# m328plain.net
KiCad netlist of a schematic drawn in EAGLE
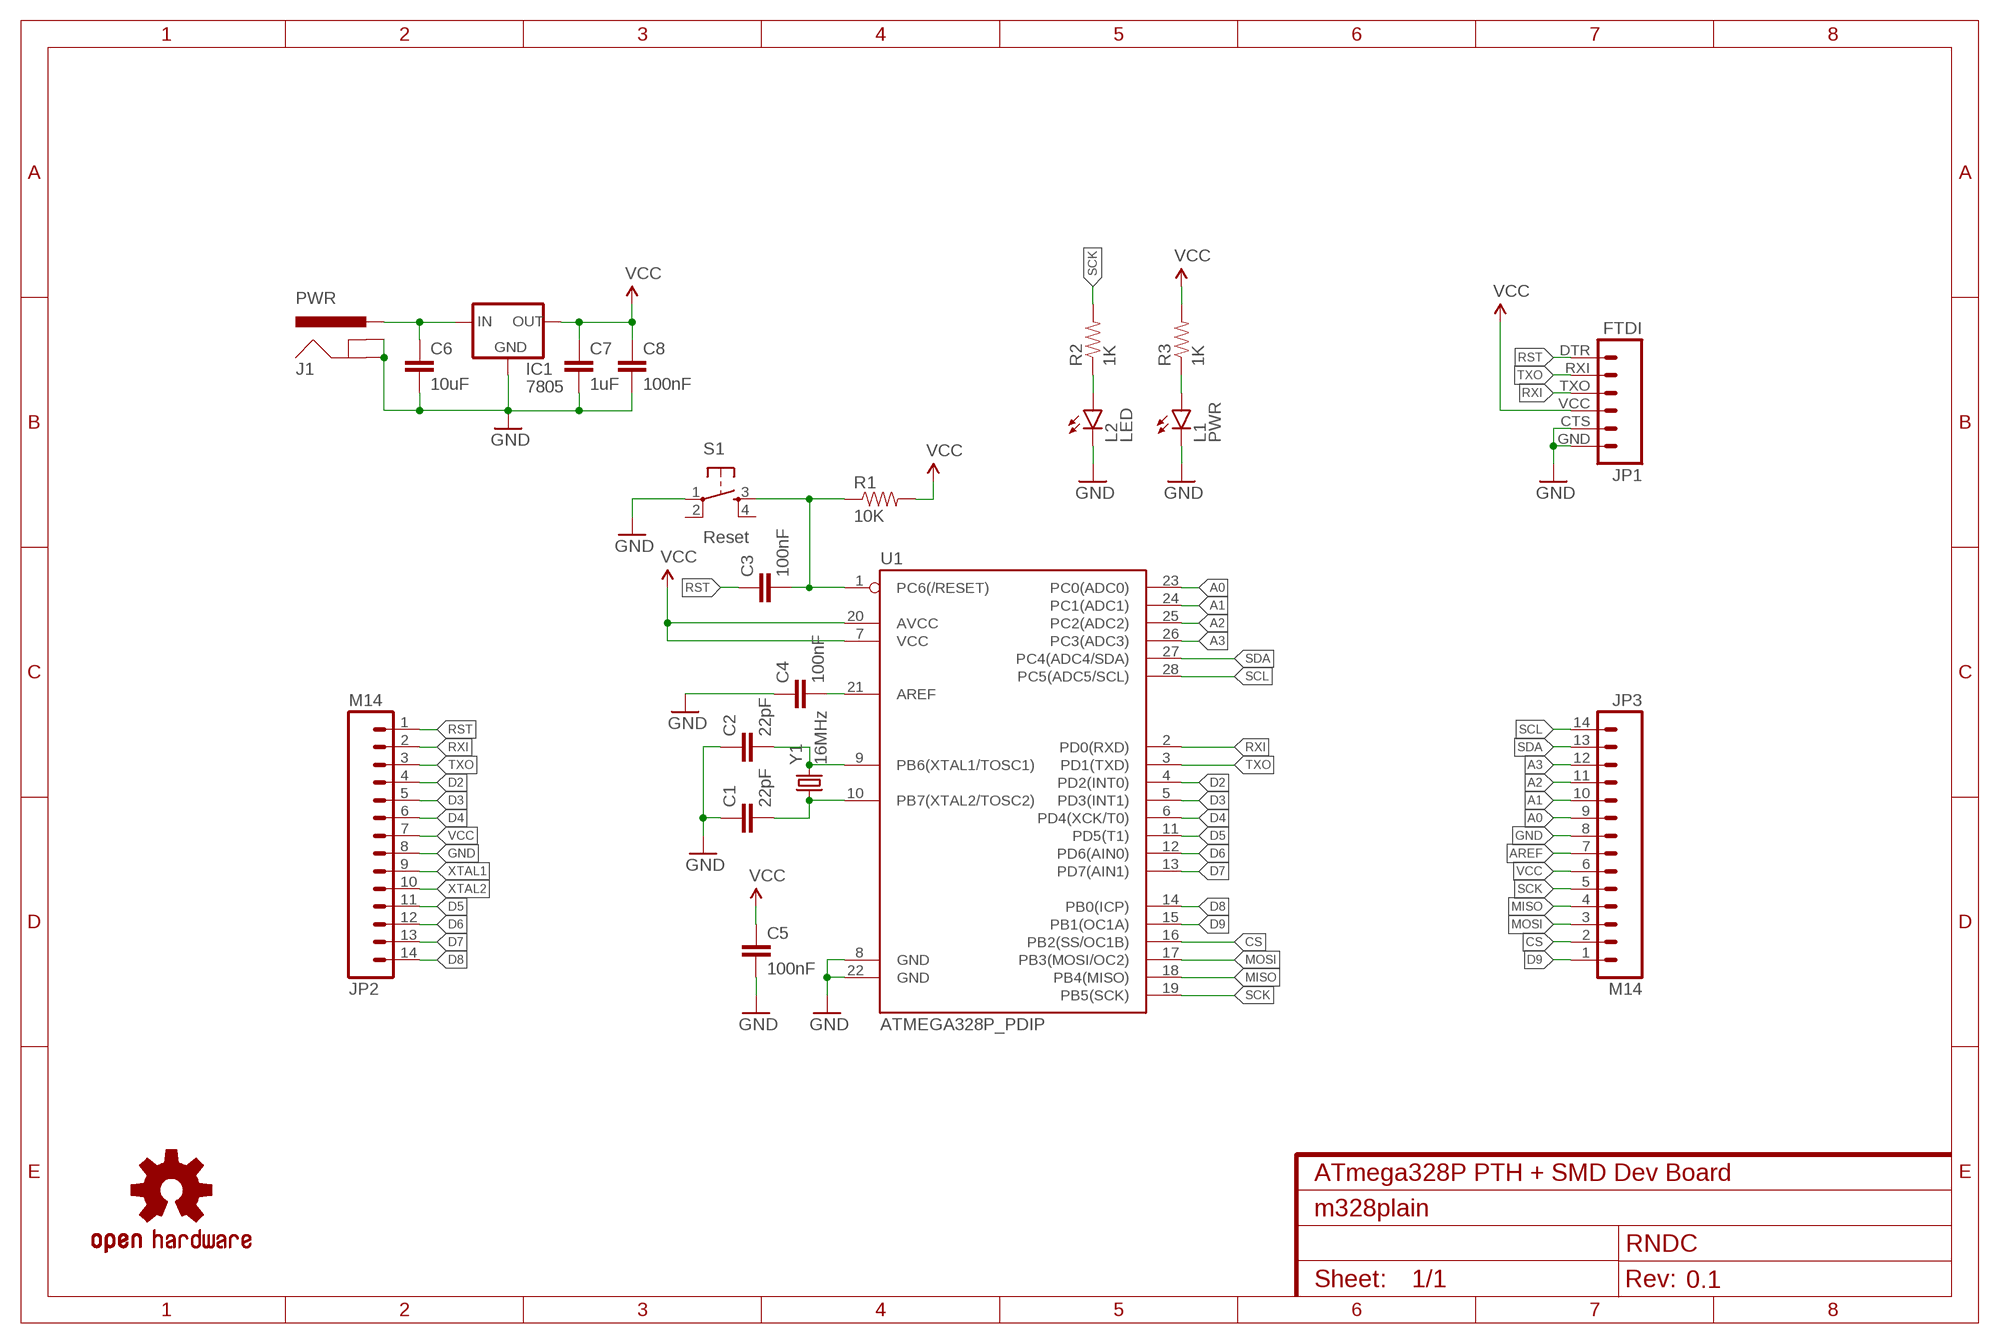
[diagram p0: schematic, sheet 1]

(export (version "E")
  (design (tool "Eeschema 10.0.6"))
  (components
    (comp (ref "C1")
      (value "22pF")
      (footprint "eagle-import:0805")
      (libsource (lib "eagle-import") (part "CAP0805"))
    )
    (comp (ref "C2")
      (value "22pF")
      (footprint "eagle-import:0805")
      (libsource (lib "eagle-import") (part "CAP0805"))
    )
    (comp (ref "C3")
      (value "100nF")
      (footprint "eagle-import:0805")
      (libsource (lib "eagle-import") (part "CAP0805"))
    )
    (comp (ref "C4")
      (value "100nF")
      (footprint "eagle-import:0805")
      (libsource (lib "eagle-import") (part "CAP0805"))
    )
    (comp (ref "C5")
      (value "100nF")
      (footprint "eagle-import:0805")
      (libsource (lib "eagle-import") (part "CAP0805"))
    )
    (comp (ref "C6")
      (value "10uF")
      (footprint "eagle-import:0603-CAP")
      (libsource (lib "eagle-import") (part "CAP0603-CAP"))
    )
    (comp (ref "C7")
      (value "1uF")
      (footprint "eagle-import:0603-CAP")
      (libsource (lib "eagle-import") (part "CAP0603-CAP"))
    )
    (comp (ref "C8")
      (value "100nF")
      (footprint "eagle-import:0805")
      (libsource (lib "eagle-import") (part "CAP0805"))
    )
    (comp (ref "IC1")
      (value "7805")
      (footprint "eagle-import:TO-92")
      (libsource (lib "eagle-import") (part "V_REG_78XXTO-92_UNTESTED"))
    )
    (comp (ref "J1")
      (value "PWR")
      (footprint "eagle-import:POWER_JACK_PTH")
      (libsource (lib "eagle-import") (part "POWER_JACKPTH"))
    )
    (comp (ref "JP1")
      (value "FTDI")
      (footprint "eagle-import:FTDI_BASIC")
      (libsource (lib "eagle-import") (part "FTDI_BASICPTH"))
    )
    (comp (ref "JP2")
      (value "M14")
      (footprint "eagle-import:1X14")
      (libsource (lib "eagle-import") (part "M14"))
    )
    (comp (ref "JP3")
      (value "M14")
      (footprint "eagle-import:1X14")
      (libsource (lib "eagle-import") (part "M14"))
    )
    (comp (ref "L1")
      (value "PWR")
      (footprint "eagle-import:LED3MM-NS")
      (libsource (lib "eagle-import") (part "LED-3MM-NO_SILK"))
    )
    (comp (ref "L2")
      (value "LED")
      (footprint "eagle-import:LED3MM-NS")
      (libsource (lib "eagle-import") (part "LED-3MM-NO_SILK"))
    )
    (comp (ref "LOGO1")
      (value "OSHW-LOGOL")
      (footprint "eagle-import:OSHW-LOGO-L")
      (libsource (lib "eagle-import") (part "OSHW-LOGOL"))
    )
    (comp (ref "R1")
      (value "10K")
      (footprint "eagle-import:0603-RES")
      (libsource (lib "eagle-import") (part "RESISTOR0603"))
    )
    (comp (ref "R2")
      (value "1K")
      (footprint "eagle-import:0603-RES")
      (libsource (lib "eagle-import") (part "RESISTOR0603-RES"))
    )
    (comp (ref "R3")
      (value "1K")
      (footprint "eagle-import:0603-RES")
      (libsource (lib "eagle-import") (part "RESISTOR0603-RES"))
    )
    (comp (ref "S1")
      (value "Reset")
      (footprint "eagle-import:TACTILE-PTH")
      (libsource (lib "eagle-import") (part "TAC_SWITCHPTH"))
    )
    (comp (ref "U1")
      (value "ATMEGA328P_PDIP")
      (footprint "eagle-import:DIL28-3")
      (libsource (lib "eagle-import") (part "ATMEGA328P_PDIP"))
    )
    (comp (ref "Y1")
      (value "16MHz")
      (footprint "eagle-import:HC49US")
      (libsource (lib "eagle-import") (part "CRYSTALHC49US"))
    )
  )
  (nets
    (net (code "1") (name "A0") (class "Default")
      (node (ref "JP3") (pin "9") (pinfunction "9_9") (pintype "passive"))
      (node (ref "U1") (pin "23") (pinfunction "PC0(ADC0)_23") (pintype "bidirectional"))
    )
    (net (code "2") (name "A1") (class "Default")
      (node (ref "JP3") (pin "10") (pinfunction "10_10") (pintype "passive"))
      (node (ref "U1") (pin "24") (pinfunction "PC1(ADC1)_24") (pintype "bidirectional"))
    )
    (net (code "3") (name "A2") (class "Default")
      (node (ref "JP3") (pin "11") (pinfunction "11_11") (pintype "passive"))
      (node (ref "U1") (pin "25") (pinfunction "PC2(ADC2)_25") (pintype "bidirectional"))
    )
    (net (code "4") (name "A3") (class "Default")
      (node (ref "JP3") (pin "12") (pinfunction "12_12") (pintype "passive"))
      (node (ref "U1") (pin "26") (pinfunction "PC3(ADC3)_26") (pintype "bidirectional"))
    )
    (net (code "5") (name "AREF") (class "Default")
      (node (ref "C4") (pin "2") (pinfunction "2_2") (pintype "passive"))
      (node (ref "JP3") (pin "7") (pinfunction "7_7") (pintype "passive"))
      (node (ref "U1") (pin "21") (pinfunction "AREF_21") (pintype "bidirectional"))
    )
    (net (code "6") (name "CS") (class "Default")
      (node (ref "JP3") (pin "2") (pinfunction "2_2") (pintype "passive"))
      (node (ref "U1") (pin "16") (pinfunction "PB2(SS/OC1B)_16") (pintype "bidirectional"))
    )
    (net (code "7") (name "D2") (class "Default")
      (node (ref "JP2") (pin "4") (pinfunction "4_4") (pintype "passive"))
      (node (ref "U1") (pin "4") (pinfunction "PD2(INT0)_4") (pintype "bidirectional"))
    )
    (net (code "8") (name "D3") (class "Default")
      (node (ref "JP2") (pin "5") (pinfunction "5_5") (pintype "passive"))
      (node (ref "U1") (pin "5") (pinfunction "PD3(INT1)_5") (pintype "bidirectional"))
    )
    (net (code "9") (name "D4") (class "Default")
      (node (ref "JP2") (pin "6") (pinfunction "6_6") (pintype "passive"))
      (node (ref "U1") (pin "6") (pinfunction "PD4(XCK/T0)_6") (pintype "bidirectional"))
    )
    (net (code "10") (name "D5") (class "Default")
      (node (ref "JP2") (pin "11") (pinfunction "11_11") (pintype "passive"))
      (node (ref "U1") (pin "11") (pinfunction "PD5(T1)_11") (pintype "bidirectional"))
    )
    (net (code "11") (name "D6") (class "Default")
      (node (ref "JP2") (pin "12") (pinfunction "12_12") (pintype "passive"))
      (node (ref "U1") (pin "12") (pinfunction "PD6(AIN0)_12") (pintype "bidirectional"))
    )
    (net (code "12") (name "D7") (class "Default")
      (node (ref "JP2") (pin "13") (pinfunction "13_13") (pintype "passive"))
      (node (ref "U1") (pin "13") (pinfunction "PD7(AIN1)_13") (pintype "bidirectional"))
    )
    (net (code "13") (name "D8") (class "Default")
      (node (ref "JP2") (pin "14") (pinfunction "14_14") (pintype "passive"))
      (node (ref "U1") (pin "14") (pinfunction "PB0(ICP)_14") (pintype "bidirectional"))
    )
    (net (code "14") (name "D9") (class "Default")
      (node (ref "JP3") (pin "1") (pinfunction "1_1") (pintype "passive"))
      (node (ref "U1") (pin "15") (pinfunction "PB1(OC1A)_15") (pintype "bidirectional"))
    )
    (net (code "15") (name "GND") (class "Default")
      (node (ref "C1") (pin "1") (pinfunction "1_1") (pintype "passive"))
      (node (ref "C2") (pin "1") (pinfunction "1_1") (pintype "passive"))
      (node (ref "C4") (pin "1") (pinfunction "1_1") (pintype "passive"))
      (node (ref "C5") (pin "2") (pinfunction "2_2") (pintype "passive"))
      (node (ref "C6") (pin "2") (pinfunction "2_2") (pintype "passive"))
      (node (ref "C7") (pin "2") (pinfunction "2_2") (pintype "passive"))
      (node (ref "C8") (pin "2") (pinfunction "2_2") (pintype "passive"))
      (node (ref "IC1") (pin "1") (pinfunction "GND_1") (pintype "input"))
      (node (ref "J1") (pin "GND") (pinfunction "GND_GND") (pintype "bidirectional"))
      (node (ref "J1") (pin "GNDBREAK") (pinfunction "GNDBREAK_GNDBREAK") (pintype "bidirectional"))
      (node (ref "JP1") (pin "CTS") (pinfunction "5_CTS") (pintype "passive"))
      (node (ref "JP1") (pin "GND") (pinfunction "6_GND") (pintype "passive"))
      (node (ref "JP2") (pin "8") (pinfunction "8_8") (pintype "passive"))
      (node (ref "JP3") (pin "8") (pinfunction "8_8") (pintype "passive"))
      (node (ref "L1") (pin "K") (pinfunction "C_K") (pintype "passive"))
      (node (ref "L2") (pin "K") (pinfunction "C_K") (pintype "passive"))
      (node (ref "S1") (pin "1") (pinfunction "1_1") (pintype "passive"))
      (node (ref "U1") (pin "22") (pinfunction "GND_22") (pintype "bidirectional"))
      (node (ref "U1") (pin "8") (pinfunction "GND_8") (pintype "bidirectional"))
    )
    (net (code "16") (name "MISO") (class "Default")
      (node (ref "JP3") (pin "4") (pinfunction "4_4") (pintype "passive"))
      (node (ref "U1") (pin "18") (pinfunction "PB4(MISO)_18") (pintype "bidirectional"))
    )
    (net (code "17") (name "MOSI") (class "Default")
      (node (ref "JP3") (pin "3") (pinfunction "3_3") (pintype "passive"))
      (node (ref "U1") (pin "17") (pinfunction "PB3(MOSI/OC2)_17") (pintype "bidirectional"))
    )
    (net (code "18") (name "Net-(IC1-IN)") (class "Default")
      (node (ref "C6") (pin "1") (pinfunction "1_1") (pintype "passive"))
      (node (ref "IC1") (pin "2") (pinfunction "IN_2") (pintype "input"))
      (node (ref "J1") (pin "PWR") (pinfunction "PWR_PWR") (pintype "bidirectional"))
    )
    (net (code "19") (name "Net-(L1-PadA)") (class "Default")
      (node (ref "L1") (pin "A") (pinfunction "A_A") (pintype "passive"))
      (node (ref "R3") (pin "1") (pinfunction "1_1") (pintype "passive"))
    )
    (net (code "20") (name "Net-(L2-PadA)") (class "Default")
      (node (ref "L2") (pin "A") (pinfunction "A_A") (pintype "passive"))
      (node (ref "R2") (pin "1") (pinfunction "1_1") (pintype "passive"))
    )
    (net (code "21") (name "Net-(U1-PC6({slash}RESET))") (class "Default")
      (node (ref "C3") (pin "2") (pinfunction "2_2") (pintype "passive"))
      (node (ref "R1") (pin "1") (pinfunction "1_1") (pintype "passive"))
      (node (ref "S1") (pin "3") (pinfunction "3_3") (pintype "passive"))
      (node (ref "U1") (pin "1") (pinfunction "PC6(/RESET)_1") (pintype "bidirectional"))
    )
    (net (code "22") (name "RST") (class "Default")
      (node (ref "C3") (pin "1") (pinfunction "1_1") (pintype "passive"))
      (node (ref "JP1") (pin "DTR") (pinfunction "1_DTR") (pintype "passive"))
      (node (ref "JP2") (pin "1") (pinfunction "1_1") (pintype "passive"))
    )
    (net (code "23") (name "RXI") (class "Default")
      (node (ref "JP1") (pin "TXO") (pinfunction "3_TXO") (pintype "passive"))
      (node (ref "JP2") (pin "2") (pinfunction "2_2") (pintype "passive"))
      (node (ref "U1") (pin "2") (pinfunction "PD0(RXD)_2") (pintype "bidirectional"))
    )
    (net (code "24") (name "SCK") (class "Default")
      (node (ref "JP3") (pin "5") (pinfunction "5_5") (pintype "passive"))
      (node (ref "R2") (pin "2") (pinfunction "2_2") (pintype "passive"))
      (node (ref "U1") (pin "19") (pinfunction "PB5(SCK)_19") (pintype "bidirectional"))
    )
    (net (code "25") (name "SCL") (class "Default")
      (node (ref "JP3") (pin "14") (pinfunction "14_14") (pintype "passive"))
      (node (ref "U1") (pin "28") (pinfunction "PC5(ADC5/SCL)_28") (pintype "bidirectional"))
    )
    (net (code "26") (name "SDA") (class "Default")
      (node (ref "JP3") (pin "13") (pinfunction "13_13") (pintype "passive"))
      (node (ref "U1") (pin "27") (pinfunction "PC4(ADC4/SDA)_27") (pintype "bidirectional"))
    )
    (net (code "27") (name "TXO") (class "Default")
      (node (ref "JP1") (pin "RXI") (pinfunction "2_RXI") (pintype "passive"))
      (node (ref "JP2") (pin "3") (pinfunction "3_3") (pintype "passive"))
      (node (ref "U1") (pin "3") (pinfunction "PD1(TXD)_3") (pintype "bidirectional"))
    )
    (net (code "28") (name "VCC") (class "Default")
      (node (ref "C5") (pin "1") (pinfunction "1_1") (pintype "passive"))
      (node (ref "C7") (pin "1") (pinfunction "1_1") (pintype "passive"))
      (node (ref "C8") (pin "1") (pinfunction "1_1") (pintype "passive"))
      (node (ref "IC1") (pin "3") (pinfunction "OUT_3") (pintype "output"))
      (node (ref "JP1") (pin "VCC") (pinfunction "4_VCC") (pintype "passive"))
      (node (ref "JP2") (pin "7") (pinfunction "7_7") (pintype "passive"))
      (node (ref "JP3") (pin "6") (pinfunction "6_6") (pintype "passive"))
      (node (ref "R1") (pin "2") (pinfunction "2_2") (pintype "passive"))
      (node (ref "R3") (pin "2") (pinfunction "2_2") (pintype "passive"))
      (node (ref "U1") (pin "20") (pinfunction "AVCC_20") (pintype "bidirectional"))
      (node (ref "U1") (pin "7") (pinfunction "VCC_7") (pintype "bidirectional"))
    )
    (net (code "29") (name "XTAL1") (class "Default")
      (node (ref "C2") (pin "2") (pinfunction "2_2") (pintype "passive"))
      (node (ref "JP2") (pin "9") (pinfunction "9_9") (pintype "passive"))
      (node (ref "U1") (pin "9") (pinfunction "PB6(XTAL1/TOSC1)_9") (pintype "bidirectional"))
      (node (ref "Y1") (pin "2") (pinfunction "2_2") (pintype "passive"))
    )
    (net (code "30") (name "XTAL2") (class "Default")
      (node (ref "C1") (pin "2") (pinfunction "2_2") (pintype "passive"))
      (node (ref "JP2") (pin "10") (pinfunction "10_10") (pintype "passive"))
      (node (ref "U1") (pin "10") (pinfunction "PB7(XTAL2/TOSC2)_10") (pintype "bidirectional"))
      (node (ref "Y1") (pin "1") (pinfunction "1_1") (pintype "passive"))
    )
    (net (code "31") (name "unconnected-(S1-Pad2)") (class "Default")
      (node (ref "S1") (pin "2") (pinfunction "2_2") (pintype "passive"))
    )
    (net (code "32") (name "unconnected-(S1-Pad4)") (class "Default")
      (node (ref "S1") (pin "4") (pinfunction "4_4") (pintype "passive"))
    )
  )
)
